# F408HS_control.net
KiCad netlist of a schematic drawn in EAGLE
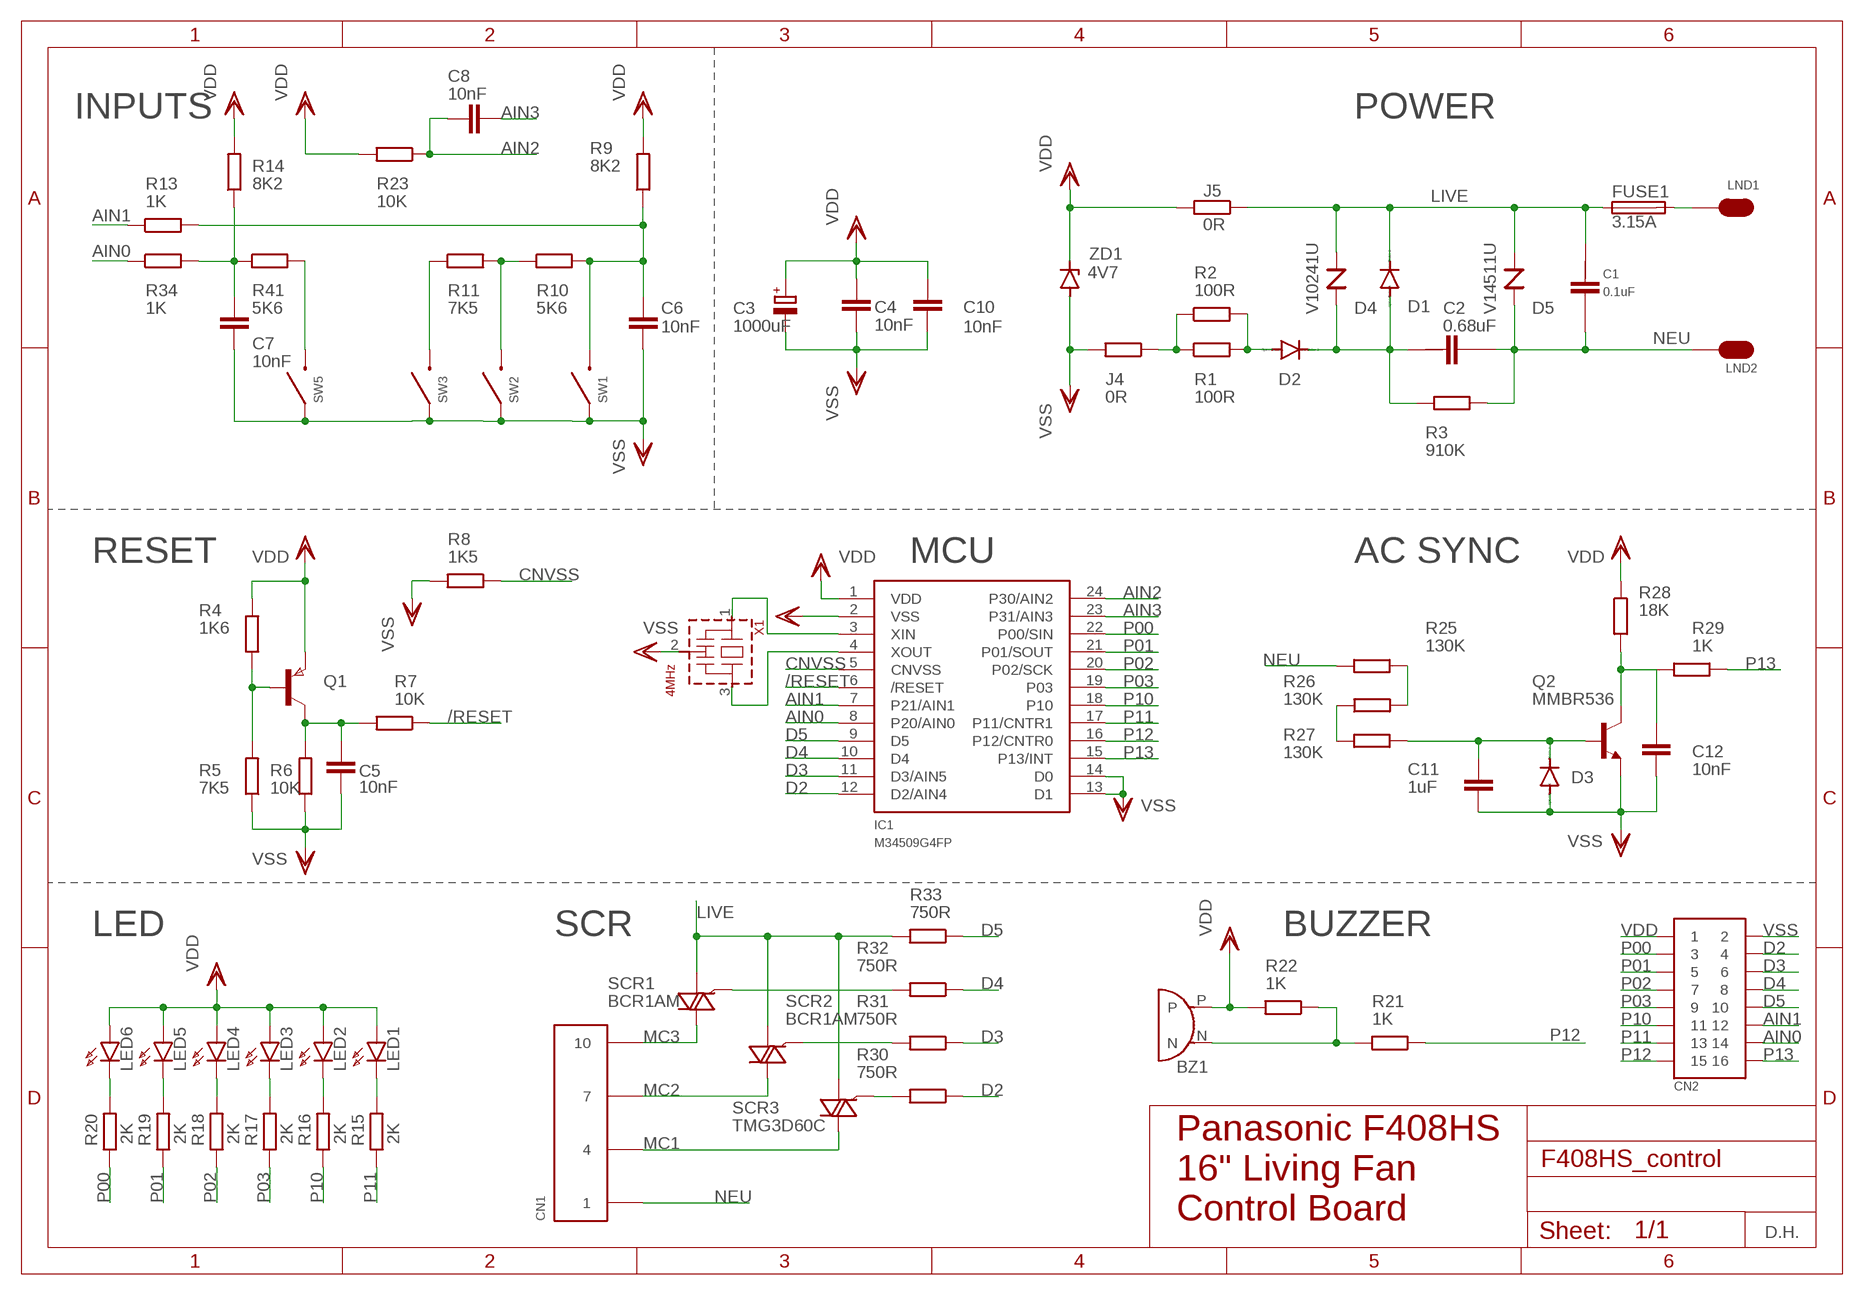
[diagram p0: schematic, sheet 1]

(export (version "E")
  (design (tool "Eeschema 10.0.6"))
  (components
    (comp (ref "BZ1")
      (value "BUZZER")
      (footprint "eagle-import:BUZZER")
      (libsource (lib "eagle-import") (part "BUZZER"))
    )
    (comp (ref "C1")
      (value "0.1uF")
      (footprint "eagle-import:ECQU2A104")
      (libsource (lib "eagle-import") (part "ECQU2A104"))
    )
    (comp (ref "C2")
      (value "0.68uF")
      (footprint "eagle-import:ECQU2A684")
      (libsource (lib "eagle-import") (part "ECQUL2A648KL"))
    )
    (comp (ref "C3")
      (value "1000uF")
      (footprint "eagle-import:B45181B")
      (libsource (lib "eagle-import") (part "CPOL-EUB45181B"))
    )
    (comp (ref "C4")
      (value "10nF")
      (footprint "eagle-import:C0805")
      (libsource (lib "eagle-import") (part "C-EUC0805"))
    )
    (comp (ref "C5")
      (value "10nF")
      (footprint "eagle-import:C0805")
      (libsource (lib "eagle-import") (part "C-EUC0805"))
    )
    (comp (ref "C6")
      (value "10nF")
      (footprint "eagle-import:C0805")
      (libsource (lib "eagle-import") (part "C-EUC0805"))
    )
    (comp (ref "C7")
      (value "10nF")
      (footprint "eagle-import:C0805")
      (libsource (lib "eagle-import") (part "C-EUC0805"))
    )
    (comp (ref "C8")
      (value "10nF")
      (footprint "eagle-import:C0805")
      (libsource (lib "eagle-import") (part "C-EUC0805"))
    )
    (comp (ref "C10")
      (value "10nF")
      (footprint "eagle-import:C0805")
      (libsource (lib "eagle-import") (part "C-EUC0805"))
    )
    (comp (ref "C11")
      (value "1uF")
      (footprint "eagle-import:C0805")
      (libsource (lib "eagle-import") (part "C-EUC0805"))
    )
    (comp (ref "C12")
      (value "10nF")
      (footprint "eagle-import:C0805")
      (libsource (lib "eagle-import") (part "C-EUC0805"))
    )
    (comp (ref "CN1")
      (value "SC25-10WS")
      (footprint "eagle-import:SC25-10WS")
      (libsource (lib "eagle-import") (part "SC25-10WS"))
    )
    (comp (ref "CN2")
      (value "HEADER16")
      (footprint "eagle-import:PAK100_2500-16")
      (libsource (lib "eagle-import") (part "HEADER16"))
    )
    (comp (ref "D1")
      (value "SD103CWS-7-F")
      (footprint "eagle-import:DO41-10")
      (libsource (lib "eagle-import") (part "1N4004"))
    )
    (comp (ref "D2")
      (value "SD103CWS-7-F")
      (footprint "eagle-import:DO41-10")
      (libsource (lib "eagle-import") (part "1N4004"))
    )
    (comp (ref "D3")
      (value "DIODE-SOD106-W")
      (footprint "eagle-import:SOD106-W")
      (libsource (lib "eagle-import") (part "DIODE-SOD106-W"))
    )
    (comp (ref "D4")
      (value "V10241U")
      (footprint "eagle-import:E14-S1")
      (libsource (lib "eagle-import") (part "TVS"))
    )
    (comp (ref "D5")
      (value "V14511U")
      (footprint "eagle-import:E14-S1")
      (libsource (lib "eagle-import") (part "TVS"))
    )
    (comp (ref "FUSE1")
      (value "3.15A")
      (footprint "eagle-import:FUSE")
      (libsource (lib "eagle-import") (part "FUSE"))
    )
    (comp (ref "IC1")
      (value "M34509G4FP")
      (footprint "eagle-import:SSOP24")
      (libsource (lib "eagle-import") (part "M34509G4FP"))
    )
    (comp (ref "J4")
      (value "0R")
      (footprint "eagle-import:M0805")
      (libsource (lib "eagle-import") (part "R-EU_M0805"))
    )
    (comp (ref "J5")
      (value "0R")
      (footprint "eagle-import:M0805")
      (libsource (lib "eagle-import") (part "R-EU_M0805"))
    )
    (comp (ref "LED1")
      (value "LED_PTH_HORIZ")
      (footprint "eagle-import:LED_HORIZ")
      (libsource (lib "eagle-import") (part "LED_PTH_HORIZ"))
    )
    (comp (ref "LED2")
      (value "LED_PTH_HORIZ")
      (footprint "eagle-import:LED_HORIZ")
      (libsource (lib "eagle-import") (part "LED_PTH_HORIZ"))
    )
    (comp (ref "LED3")
      (value "LED_PTH_HORIZ")
      (footprint "eagle-import:LED_HORIZ")
      (libsource (lib "eagle-import") (part "LED_PTH_HORIZ"))
    )
    (comp (ref "LED4")
      (value "LED_PTH_HORIZ")
      (footprint "eagle-import:LED_HORIZ")
      (libsource (lib "eagle-import") (part "LED_PTH_HORIZ"))
    )
    (comp (ref "LED5")
      (value "LED_PTH_HORIZ")
      (footprint "eagle-import:LED_HORIZ")
      (libsource (lib "eagle-import") (part "LED_PTH_HORIZ"))
    )
    (comp (ref "LED6")
      (value "LED_PTH_HORIZ")
      (footprint "eagle-import:LED_HORIZ")
      (libsource (lib "eagle-import") (part "LED_PTH_HORIZ"))
    )
    (comp (ref "LND1")
      (value "LND")
      (footprint "eagle-import:LND")
      (libsource (lib "eagle-import") (part "LND"))
    )
    (comp (ref "LND2")
      (value "LND")
      (footprint "eagle-import:LND")
      (libsource (lib "eagle-import") (part "LND"))
    )
    (comp (ref "Q1")
      (value "PNPSOT23")
      (footprint "eagle-import:SOT-23")
      (fields (field (name "MPN") "DSS20200L-7"))
      (libsource (lib "eagle-import") (part "PNPSOT23"))
    )
    (comp (ref "Q2")
      (value "MMBR536")
      (footprint "eagle-import:SOT23")
      (libsource (lib "eagle-import") (part "MMBR536"))
    )
    (comp (ref "R1")
      (value "100R")
      (footprint "eagle-import:0204_7")
      (libsource (lib "eagle-import") (part "R-EU_0204/7"))
    )
    (comp (ref "R2")
      (value "100R")
      (footprint "eagle-import:0204_7")
      (libsource (lib "eagle-import") (part "R-EU_0204/7"))
    )
    (comp (ref "R3")
      (value "910K")
      (footprint "eagle-import:0204_7")
      (libsource (lib "eagle-import") (part "R-EU_0204/7"))
    )
    (comp (ref "R4")
      (value "1K6")
      (footprint "eagle-import:M0805")
      (libsource (lib "eagle-import") (part "R-EU_M0805"))
    )
    (comp (ref "R5")
      (value "7K5")
      (footprint "eagle-import:M0805")
      (libsource (lib "eagle-import") (part "R-EU_M0805"))
    )
    (comp (ref "R6")
      (value "10K")
      (footprint "eagle-import:M0805")
      (libsource (lib "eagle-import") (part "R-EU_M0805"))
    )
    (comp (ref "R7")
      (value "10K")
      (footprint "eagle-import:M0805")
      (libsource (lib "eagle-import") (part "R-EU_M0805"))
    )
    (comp (ref "R8")
      (value "1K5")
      (footprint "eagle-import:M0805")
      (libsource (lib "eagle-import") (part "R-EU_M0805"))
    )
    (comp (ref "R9")
      (value "8K2")
      (footprint "eagle-import:M0805")
      (libsource (lib "eagle-import") (part "R-EU_M0805"))
    )
    (comp (ref "R10")
      (value "5K6")
      (footprint "eagle-import:M0805")
      (libsource (lib "eagle-import") (part "R-EU_M0805"))
    )
    (comp (ref "R11")
      (value "7K5")
      (footprint "eagle-import:M0805")
      (libsource (lib "eagle-import") (part "R-EU_M0805"))
    )
    (comp (ref "R13")
      (value "1K")
      (footprint "eagle-import:M0805")
      (libsource (lib "eagle-import") (part "R-EU_M0805"))
    )
    (comp (ref "R14")
      (value "8K2")
      (footprint "eagle-import:M0805")
      (libsource (lib "eagle-import") (part "R-EU_M0805"))
    )
    (comp (ref "R15")
      (value "2K")
      (footprint "eagle-import:M0805")
      (libsource (lib "eagle-import") (part "R-EU_M0805"))
    )
    (comp (ref "R16")
      (value "2K")
      (footprint "eagle-import:M0805")
      (libsource (lib "eagle-import") (part "R-EU_M0805"))
    )
    (comp (ref "R17")
      (value "2K")
      (footprint "eagle-import:M0805")
      (libsource (lib "eagle-import") (part "R-EU_M0805"))
    )
    (comp (ref "R18")
      (value "2K")
      (footprint "eagle-import:M0805")
      (libsource (lib "eagle-import") (part "R-EU_M0805"))
    )
    (comp (ref "R19")
      (value "2K")
      (footprint "eagle-import:M0805")
      (libsource (lib "eagle-import") (part "R-EU_M0805"))
    )
    (comp (ref "R20")
      (value "2K")
      (footprint "eagle-import:M0805")
      (libsource (lib "eagle-import") (part "R-EU_M0805"))
    )
    (comp (ref "R21")
      (value "1K")
      (footprint "eagle-import:M0805")
      (libsource (lib "eagle-import") (part "R-EU_M0805"))
    )
    (comp (ref "R22")
      (value "1K")
      (footprint "eagle-import:M0805")
      (libsource (lib "eagle-import") (part "R-EU_M0805"))
    )
    (comp (ref "R23")
      (value "10K")
      (footprint "eagle-import:M0805")
      (libsource (lib "eagle-import") (part "R-EU_M0805"))
    )
    (comp (ref "R25")
      (value "130K")
      (footprint "eagle-import:R0805")
      (libsource (lib "eagle-import") (part "R-EU_R0805"))
    )
    (comp (ref "R26")
      (value "130K")
      (footprint "eagle-import:R0805")
      (libsource (lib "eagle-import") (part "R-EU_R0805"))
    )
    (comp (ref "R27")
      (value "130K")
      (footprint "eagle-import:R0805")
      (libsource (lib "eagle-import") (part "R-EU_R0805"))
    )
    (comp (ref "R28")
      (value "18K")
      (footprint "eagle-import:M0805")
      (libsource (lib "eagle-import") (part "R-EU_M0805"))
    )
    (comp (ref "R29")
      (value "1K")
      (footprint "eagle-import:M0805")
      (libsource (lib "eagle-import") (part "R-EU_M0805"))
    )
    (comp (ref "R30")
      (value "750R")
      (footprint "eagle-import:M0805")
      (libsource (lib "eagle-import") (part "R-EU_M0805"))
    )
    (comp (ref "R31")
      (value "750R")
      (footprint "eagle-import:M0805")
      (libsource (lib "eagle-import") (part "R-EU_M0805"))
    )
    (comp (ref "R32")
      (value "750R")
      (footprint "eagle-import:M0805")
      (libsource (lib "eagle-import") (part "R-EU_M0805"))
    )
    (comp (ref "R33")
      (value "750R")
      (footprint "eagle-import:M0805")
      (libsource (lib "eagle-import") (part "R-EU_M0805"))
    )
    (comp (ref "R34")
      (value "1K")
      (footprint "eagle-import:M0805")
      (libsource (lib "eagle-import") (part "R-EU_M0805"))
    )
    (comp (ref "R41")
      (value "5K6")
      (footprint "eagle-import:M0805")
      (libsource (lib "eagle-import") (part "R-EU_M0805"))
    )
    (comp (ref "SCR1")
      (value "BCR1AM")
      (footprint "eagle-import:TO92")
      (libsource (lib "eagle-import") (part "BCR1AM"))
    )
    (comp (ref "SCR2")
      (value "BCR1AM")
      (footprint "eagle-import:TO92")
      (libsource (lib "eagle-import") (part "BCR1AM"))
    )
    (comp (ref "SCR3")
      (value "TMG3D60C")
      (footprint "eagle-import:TO220DS")
      (libsource (lib "eagle-import") (part "TIC225S"))
    )
    (comp (ref "SW1")
      (value "EVQ11")
      (footprint "eagle-import:EVQ11")
      (libsource (lib "eagle-import") (part "EVQ11"))
    )
    (comp (ref "SW2")
      (value "EVQ11")
      (footprint "eagle-import:EVQ11")
      (libsource (lib "eagle-import") (part "EVQ11"))
    )
    (comp (ref "SW3")
      (value "EVQ11")
      (footprint "eagle-import:EVQ11")
      (libsource (lib "eagle-import") (part "EVQ11"))
    )
    (comp (ref "SW5")
      (value "EVQ11")
      (footprint "eagle-import:EVQ11")
      (libsource (lib "eagle-import") (part "EVQ11"))
    )
    (comp (ref "X1")
      (value "4MHz")
      (footprint "eagle-import:CSTLS_G9")
      (libsource (lib "eagle-import") (part "murata-resonators_CSTLS_G"))
    )
    (comp (ref "ZD1")
      (value "DDZ4V7ASF-7")
      (footprint "eagle-import:DO35Z10")
      (libsource (lib "eagle-import") (part "1N821"))
    )
  )
  (nets
    (net (code "1") (name "/AIN0") (class "Default")
      (node (ref "CN2") (pin "14") (pinfunction "14_14") (pintype "bidirectional"))
      (node (ref "IC1") (pin "8") (pinfunction "P20/AIN0_8") (pintype "bidirectional"))
      (node (ref "R34") (pin "1") (pinfunction "1_1") (pintype "passive"))
    )
    (net (code "2") (name "/AIN1") (class "Default")
      (node (ref "CN2") (pin "12") (pinfunction "12_12") (pintype "bidirectional"))
      (node (ref "IC1") (pin "7") (pinfunction "P21/AIN1_7") (pintype "bidirectional"))
      (node (ref "R13") (pin "1") (pinfunction "1_1") (pintype "passive"))
    )
    (net (code "3") (name "/AIN2") (class "Default")
      (node (ref "C8") (pin "1") (pinfunction "1_1") (pintype "passive"))
      (node (ref "IC1") (pin "24") (pinfunction "P30/AIN2_24") (pintype "bidirectional"))
      (node (ref "R23") (pin "1") (pinfunction "1_1") (pintype "passive"))
    )
    (net (code "4") (name "/AIN3") (class "Default")
      (node (ref "C8") (pin "2") (pinfunction "2_2") (pintype "passive"))
      (node (ref "IC1") (pin "23") (pinfunction "P31/AIN3_23") (pintype "bidirectional"))
    )
    (net (code "5") (name "/CNVSS") (class "Default")
      (node (ref "IC1") (pin "5") (pinfunction "CNVSS_5") (pintype "bidirectional"))
      (node (ref "R8") (pin "1") (pinfunction "1_1") (pintype "passive"))
    )
    (net (code "6") (name "/D2") (class "Default")
      (node (ref "CN2") (pin "4") (pinfunction "4_4") (pintype "bidirectional"))
      (node (ref "IC1") (pin "12") (pinfunction "D2/AIN4_12") (pintype "bidirectional"))
      (node (ref "R30") (pin "1") (pinfunction "1_1") (pintype "passive"))
    )
    (net (code "7") (name "/D3") (class "Default")
      (node (ref "CN2") (pin "6") (pinfunction "6_6") (pintype "bidirectional"))
      (node (ref "IC1") (pin "11") (pinfunction "D3/AIN5_11") (pintype "bidirectional"))
      (node (ref "R31") (pin "1") (pinfunction "1_1") (pintype "passive"))
    )
    (net (code "8") (name "/D4") (class "Default")
      (node (ref "CN2") (pin "8") (pinfunction "8_8") (pintype "bidirectional"))
      (node (ref "IC1") (pin "10") (pinfunction "D4_10") (pintype "bidirectional"))
      (node (ref "R32") (pin "1") (pinfunction "1_1") (pintype "passive"))
    )
    (net (code "9") (name "/D5") (class "Default")
      (node (ref "CN2") (pin "10") (pinfunction "10_10") (pintype "bidirectional"))
      (node (ref "IC1") (pin "9") (pinfunction "D5_9") (pintype "bidirectional"))
      (node (ref "R33") (pin "1") (pinfunction "1_1") (pintype "passive"))
    )
    (net (code "10") (name "/LIVE") (class "Default")
      (node (ref "C1") (pin "P$1") (pinfunction "P$1_P$1") (pintype "bidirectional"))
      (node (ref "D1") (pin "C") (pinfunction "C_C") (pintype "passive"))
      (node (ref "D4") (pin "P$1") (pinfunction "P$1_P$1") (pintype "bidirectional"))
      (node (ref "D5") (pin "P$1") (pinfunction "P$1_P$1") (pintype "bidirectional"))
      (node (ref "FUSE1") (pin "P$1") (pinfunction "1_P$1") (pintype "passive"))
      (node (ref "J5") (pin "1") (pinfunction "1_1") (pintype "passive"))
      (node (ref "R33") (pin "2") (pinfunction "2_2") (pintype "passive"))
      (node (ref "SCR1") (pin "1") (pinfunction "A1_1") (pintype "passive"))
      (node (ref "SCR2") (pin "1") (pinfunction "A1_1") (pintype "passive"))
      (node (ref "SCR3") (pin "A1") (pinfunction "A1_A1") (pintype "passive"))
    )
    (net (code "11") (name "/MC1") (class "Default")
      (node (ref "CN1") (pin "P$4") (pinfunction "4_P$4") (pintype "bidirectional"))
      (node (ref "SCR3") (pin "A2") (pinfunction "A2_A2") (pintype "passive"))
    )
    (net (code "12") (name "/MC2") (class "Default")
      (node (ref "CN1") (pin "P$7") (pinfunction "7_P$7") (pintype "bidirectional"))
      (node (ref "SCR2") (pin "3") (pinfunction "A2_3") (pintype "passive"))
    )
    (net (code "13") (name "/MC3") (class "Default")
      (node (ref "CN1") (pin "P$10") (pinfunction "10_P$10") (pintype "bidirectional"))
      (node (ref "SCR1") (pin "3") (pinfunction "A2_3") (pintype "passive"))
    )
    (net (code "14") (name "/NEU") (class "Default")
      (node (ref "C1") (pin "P$2") (pinfunction "P$2_P$2") (pintype "bidirectional"))
      (node (ref "C2") (pin "P$2") (pinfunction "P$2_P$2") (pintype "bidirectional"))
      (node (ref "CN1") (pin "P$1") (pinfunction "1_P$1") (pintype "bidirectional"))
      (node (ref "D5") (pin "P$2") (pinfunction "P$2_P$2") (pintype "bidirectional"))
      (node (ref "LND2") (pin "P$1") (pinfunction "P$1_P$1") (pintype "bidirectional"))
      (node (ref "R25") (pin "2") (pinfunction "2_2") (pintype "passive"))
      (node (ref "R3") (pin "2") (pinfunction "2_2") (pintype "passive"))
    )
    (net (code "15") (name "/P00") (class "Default")
      (node (ref "CN2") (pin "3") (pinfunction "3_3") (pintype "bidirectional"))
      (node (ref "IC1") (pin "22") (pinfunction "P00/SIN_22") (pintype "bidirectional"))
      (node (ref "R20") (pin "1") (pinfunction "1_1") (pintype "passive"))
    )
    (net (code "16") (name "/P01") (class "Default")
      (node (ref "CN2") (pin "5") (pinfunction "5_5") (pintype "bidirectional"))
      (node (ref "IC1") (pin "21") (pinfunction "P01/SOUT_21") (pintype "bidirectional"))
      (node (ref "R19") (pin "1") (pinfunction "1_1") (pintype "passive"))
    )
    (net (code "17") (name "/P02") (class "Default")
      (node (ref "CN2") (pin "7") (pinfunction "7_7") (pintype "bidirectional"))
      (node (ref "IC1") (pin "20") (pinfunction "P02/SCK_20") (pintype "bidirectional"))
      (node (ref "R18") (pin "1") (pinfunction "1_1") (pintype "passive"))
    )
    (net (code "18") (name "/P03") (class "Default")
      (node (ref "CN2") (pin "9") (pinfunction "9_9") (pintype "bidirectional"))
      (node (ref "IC1") (pin "19") (pinfunction "P03_19") (pintype "bidirectional"))
      (node (ref "R17") (pin "1") (pinfunction "1_1") (pintype "passive"))
    )
    (net (code "19") (name "/P10") (class "Default")
      (node (ref "CN2") (pin "11") (pinfunction "11_11") (pintype "bidirectional"))
      (node (ref "IC1") (pin "18") (pinfunction "P10_18") (pintype "bidirectional"))
      (node (ref "R16") (pin "1") (pinfunction "1_1") (pintype "passive"))
    )
    (net (code "20") (name "/P11") (class "Default")
      (node (ref "CN2") (pin "13") (pinfunction "13_13") (pintype "bidirectional"))
      (node (ref "IC1") (pin "17") (pinfunction "P11/CNTR1_17") (pintype "bidirectional"))
      (node (ref "R15") (pin "1") (pinfunction "1_1") (pintype "passive"))
    )
    (net (code "21") (name "/P12") (class "Default")
      (node (ref "CN2") (pin "15") (pinfunction "15_15") (pintype "bidirectional"))
      (node (ref "IC1") (pin "16") (pinfunction "P12/CNTR0_16") (pintype "bidirectional"))
      (node (ref "R21") (pin "1") (pinfunction "1_1") (pintype "passive"))
    )
    (net (code "22") (name "/P13") (class "Default")
      (node (ref "CN2") (pin "16") (pinfunction "16_16") (pintype "bidirectional"))
      (node (ref "IC1") (pin "15") (pinfunction "P13/INT_15") (pintype "bidirectional"))
      (node (ref "R29") (pin "1") (pinfunction "1_1") (pintype "passive"))
    )
    (net (code "23") (name "/{slash}RESET") (class "Default")
      (node (ref "IC1") (pin "6") (pinfunction "/RESET_6") (pintype "bidirectional"))
      (node (ref "R7") (pin "1") (pinfunction "1_1") (pintype "passive"))
    )
    (net (code "24") (name "Net-(BZ1-PadN)") (class "Default")
      (node (ref "BZ1") (pin "N") (pinfunction "N_N") (pintype "bidirectional"))
      (node (ref "R21") (pin "2") (pinfunction "2_2") (pintype "passive"))
      (node (ref "R22") (pin "1") (pinfunction "1_1") (pintype "passive"))
    )
    (net (code "25") (name "Net-(C2-PadP$1)") (class "Default")
      (node (ref "C2") (pin "P$1") (pinfunction "P$1_P$1") (pintype "bidirectional"))
      (node (ref "D1") (pin "A") (pinfunction "A_A") (pintype "passive"))
      (node (ref "D2") (pin "C") (pinfunction "C_C") (pintype "passive"))
      (node (ref "D4") (pin "P$2") (pinfunction "P$2_P$2") (pintype "bidirectional"))
      (node (ref "R3") (pin "1") (pinfunction "1_1") (pintype "passive"))
    )
    (net (code "26") (name "Net-(C6-Pad2)") (class "Default")
      (node (ref "C6") (pin "2") (pinfunction "2_2") (pintype "passive"))
      (node (ref "R10") (pin "2") (pinfunction "2_2") (pintype "passive"))
      (node (ref "R13") (pin "2") (pinfunction "2_2") (pintype "passive"))
      (node (ref "R9") (pin "1") (pinfunction "1_1") (pintype "passive"))
      (node (ref "SW1") (pin "P$2") (pinfunction "P$2_P$2") (pintype "bidirectional"))
    )
    (net (code "27") (name "Net-(C7-Pad1)") (class "Default")
      (node (ref "C7") (pin "1") (pinfunction "1_1") (pintype "passive"))
      (node (ref "R14") (pin "1") (pinfunction "1_1") (pintype "passive"))
      (node (ref "R34") (pin "2") (pinfunction "2_2") (pintype "passive"))
      (node (ref "R41") (pin "1") (pinfunction "1_1") (pintype "passive"))
    )
    (net (code "28") (name "Net-(D2-PadA)") (class "Default")
      (node (ref "D2") (pin "A") (pinfunction "A_A") (pintype "passive"))
      (node (ref "R1") (pin "2") (pinfunction "2_2") (pintype "passive"))
      (node (ref "R2") (pin "2") (pinfunction "2_2") (pintype "passive"))
    )
    (net (code "29") (name "Net-(FUSE1-2)") (class "Default")
      (node (ref "FUSE1") (pin "P$2") (pinfunction "2_P$2") (pintype "passive"))
      (node (ref "LND1") (pin "P$1") (pinfunction "P$1_P$1") (pintype "bidirectional"))
    )
    (net (code "30") (name "Net-(IC1-XIN)") (class "Default")
      (node (ref "IC1") (pin "3") (pinfunction "XIN_3") (pintype "bidirectional"))
      (node (ref "X1") (pin "1") (pinfunction "1_1") (pintype "output"))
    )
    (net (code "31") (name "Net-(IC1-XOUT)") (class "Default")
      (node (ref "IC1") (pin "4") (pinfunction "XOUT_4") (pintype "bidirectional"))
      (node (ref "X1") (pin "3") (pinfunction "3_3") (pintype "input"))
    )
    (net (code "32") (name "Net-(J4-Pad1)") (class "Default")
      (node (ref "J4") (pin "1") (pinfunction "1_1") (pintype "passive"))
      (node (ref "R1") (pin "1") (pinfunction "1_1") (pintype "passive"))
      (node (ref "R2") (pin "1") (pinfunction "1_1") (pintype "passive"))
    )
    (net (code "33") (name "Net-(LED1-K)") (class "Default")
      (node (ref "LED1") (pin "N") (pinfunction "K_N") (pintype "passive"))
      (node (ref "R15") (pin "2") (pinfunction "2_2") (pintype "passive"))
    )
    (net (code "34") (name "Net-(LED2-K)") (class "Default")
      (node (ref "LED2") (pin "N") (pinfunction "K_N") (pintype "passive"))
      (node (ref "R16") (pin "2") (pinfunction "2_2") (pintype "passive"))
    )
    (net (code "35") (name "Net-(LED3-K)") (class "Default")
      (node (ref "LED3") (pin "N") (pinfunction "K_N") (pintype "passive"))
      (node (ref "R17") (pin "2") (pinfunction "2_2") (pintype "passive"))
    )
    (net (code "36") (name "Net-(LED4-K)") (class "Default")
      (node (ref "LED4") (pin "N") (pinfunction "K_N") (pintype "passive"))
      (node (ref "R18") (pin "2") (pinfunction "2_2") (pintype "passive"))
    )
    (net (code "37") (name "Net-(LED5-K)") (class "Default")
      (node (ref "LED5") (pin "N") (pinfunction "K_N") (pintype "passive"))
      (node (ref "R19") (pin "2") (pinfunction "2_2") (pintype "passive"))
    )
    (net (code "38") (name "Net-(LED6-K)") (class "Default")
      (node (ref "LED6") (pin "N") (pinfunction "K_N") (pintype "passive"))
      (node (ref "R20") (pin "2") (pinfunction "2_2") (pintype "passive"))
    )
    (net (code "39") (name "Net-(Q1-B)") (class "Default")
      (node (ref "Q1") (pin "3") (pinfunction "B_3") (pintype "passive"))
      (node (ref "R4") (pin "1") (pinfunction "1_1") (pintype "passive"))
      (node (ref "R5") (pin "2") (pinfunction "2_2") (pintype "passive"))
    )
    (net (code "40") (name "Net-(Q1-C)") (class "Default")
      (node (ref "C5") (pin "1") (pinfunction "1_1") (pintype "passive"))
      (node (ref "Q1") (pin "1") (pinfunction "C_1") (pintype "passive"))
      (node (ref "R6") (pin "2") (pinfunction "2_2") (pintype "passive"))
      (node (ref "R7") (pin "2") (pinfunction "2_2") (pintype "passive"))
    )
    (net (code "41") (name "Net-(Q2-B)") (class "Default")
      (node (ref "C11") (pin "2") (pinfunction "2_2") (pintype "passive"))
      (node (ref "D3") (pin "C") (pinfunction "C_C") (pintype "passive"))
      (node (ref "Q2") (pin "1") (pinfunction "B_1") (pintype "passive"))
      (node (ref "R27") (pin "1") (pinfunction "1_1") (pintype "passive"))
    )
    (net (code "42") (name "Net-(Q2-C)") (class "Default")
      (node (ref "C12") (pin "2") (pinfunction "2_2") (pintype "passive"))
      (node (ref "Q2") (pin "3") (pinfunction "C_3") (pintype "passive"))
      (node (ref "R28") (pin "2") (pinfunction "2_2") (pintype "passive"))
      (node (ref "R29") (pin "2") (pinfunction "2_2") (pintype "passive"))
    )
    (net (code "43") (name "Net-(R10-Pad1)") (class "Default")
      (node (ref "R10") (pin "1") (pinfunction "1_1") (pintype "passive"))
      (node (ref "R11") (pin "2") (pinfunction "2_2") (pintype "passive"))
      (node (ref "SW2") (pin "P$2") (pinfunction "P$2_P$2") (pintype "bidirectional"))
    )
    (net (code "44") (name "Net-(R11-Pad1)") (class "Default")
      (node (ref "R11") (pin "1") (pinfunction "1_1") (pintype "passive"))
      (node (ref "SW3") (pin "P$2") (pinfunction "P$2_P$2") (pintype "bidirectional"))
    )
    (net (code "45") (name "Net-(R25-Pad1)") (class "Default")
      (node (ref "R25") (pin "1") (pinfunction "1_1") (pintype "passive"))
      (node (ref "R26") (pin "2") (pinfunction "2_2") (pintype "passive"))
    )
    (net (code "46") (name "Net-(R26-Pad1)") (class "Default")
      (node (ref "R26") (pin "1") (pinfunction "1_1") (pintype "passive"))
      (node (ref "R27") (pin "2") (pinfunction "2_2") (pintype "passive"))
    )
    (net (code "47") (name "Net-(R30-Pad2)") (class "Default")
      (node (ref "R30") (pin "2") (pinfunction "2_2") (pintype "passive"))
      (node (ref "SCR3") (pin "G") (pinfunction "G_G") (pintype "passive"))
    )
    (net (code "48") (name "Net-(R41-Pad2)") (class "Default")
      (node (ref "R41") (pin "2") (pinfunction "2_2") (pintype "passive"))
      (node (ref "SW5") (pin "P$2") (pinfunction "P$2_P$2") (pintype "bidirectional"))
    )
    (net (code "49") (name "Net-(SCR1-G)") (class "Default")
      (node (ref "R32") (pin "2") (pinfunction "2_2") (pintype "passive"))
      (node (ref "SCR1") (pin "2") (pinfunction "G_2") (pintype "passive"))
    )
    (net (code "50") (name "Net-(SCR2-G)") (class "Default")
      (node (ref "R31") (pin "2") (pinfunction "2_2") (pintype "passive"))
      (node (ref "SCR2") (pin "2") (pinfunction "G_2") (pintype "passive"))
    )
    (net (code "51") (name "VDD") (class "Default")
      (node (ref "BZ1") (pin "P") (pinfunction "P_P") (pintype "bidirectional"))
      (node (ref "C10") (pin "1") (pinfunction "1_1") (pintype "passive"))
      (node (ref "C3") (pin "+") (pinfunction "+_+") (pintype "passive"))
      (node (ref "C4") (pin "1") (pinfunction "1_1") (pintype "passive"))
      (node (ref "CN2") (pin "1") (pinfunction "1_1") (pintype "bidirectional"))
      (node (ref "IC1") (pin "1") (pinfunction "VDD_1") (pintype "bidirectional"))
      (node (ref "J5") (pin "2") (pinfunction "2_2") (pintype "passive"))
      (node (ref "LED1") (pin "P") (pinfunction "A_P") (pintype "passive"))
      (node (ref "LED2") (pin "P") (pinfunction "A_P") (pintype "passive"))
      (node (ref "LED3") (pin "P") (pinfunction "A_P") (pintype "passive"))
      (node (ref "LED4") (pin "P") (pinfunction "A_P") (pintype "passive"))
      (node (ref "LED5") (pin "P") (pinfunction "A_P") (pintype "passive"))
      (node (ref "LED6") (pin "P") (pinfunction "A_P") (pintype "passive"))
      (node (ref "Q1") (pin "2") (pinfunction "E_2") (pintype "passive"))
      (node (ref "R14") (pin "2") (pinfunction "2_2") (pintype "passive"))
      (node (ref "R22") (pin "2") (pinfunction "2_2") (pintype "passive"))
      (node (ref "R23") (pin "2") (pinfunction "2_2") (pintype "passive"))
      (node (ref "R28") (pin "1") (pinfunction "1_1") (pintype "passive"))
      (node (ref "R4") (pin "2") (pinfunction "2_2") (pintype "passive"))
      (node (ref "R9") (pin "2") (pinfunction "2_2") (pintype "passive"))
      (node (ref "ZD1") (pin "C") (pinfunction "C_C") (pintype "passive"))
    )
    (net (code "52") (name "VSS") (class "Default")
      (node (ref "C10") (pin "2") (pinfunction "2_2") (pintype "passive"))
      (node (ref "C11") (pin "1") (pinfunction "1_1") (pintype "passive"))
      (node (ref "C12") (pin "1") (pinfunction "1_1") (pintype "passive"))
      (node (ref "C3") (pin "-") (pinfunction "-_-") (pintype "passive"))
      (node (ref "C4") (pin "2") (pinfunction "2_2") (pintype "passive"))
      (node (ref "C5") (pin "2") (pinfunction "2_2") (pintype "passive"))
      (node (ref "C6") (pin "1") (pinfunction "1_1") (pintype "passive"))
      (node (ref "C7") (pin "2") (pinfunction "2_2") (pintype "passive"))
      (node (ref "CN2") (pin "2") (pinfunction "2_2") (pintype "bidirectional"))
      (node (ref "D3") (pin "A") (pinfunction "A_A") (pintype "passive"))
      (node (ref "IC1") (pin "13") (pinfunction "D1_13") (pintype "bidirectional"))
      (node (ref "IC1") (pin "14") (pinfunction "D0_14") (pintype "bidirectional"))
      (node (ref "IC1") (pin "2") (pinfunction "VSS_2") (pintype "bidirectional"))
      (node (ref "J4") (pin "2") (pinfunction "2_2") (pintype "passive"))
      (node (ref "Q2") (pin "2") (pinfunction "E_2") (pintype "passive"))
      (node (ref "R5") (pin "1") (pinfunction "1_1") (pintype "passive"))
      (node (ref "R6") (pin "1") (pinfunction "1_1") (pintype "passive"))
      (node (ref "R8") (pin "2") (pinfunction "2_2") (pintype "passive"))
      (node (ref "SW1") (pin "P$1") (pinfunction "P$1_P$1") (pintype "bidirectional"))
      (node (ref "SW2") (pin "P$1") (pinfunction "P$1_P$1") (pintype "bidirectional"))
      (node (ref "SW3") (pin "P$1") (pinfunction "P$1_P$1") (pintype "bidirectional"))
      (node (ref "SW5") (pin "P$1") (pinfunction "P$1_P$1") (pintype "bidirectional"))
      (node (ref "X1") (pin "2") (pinfunction "VSS_2") (pintype "power_in"))
      (node (ref "ZD1") (pin "A") (pinfunction "A_A") (pintype "passive"))
    )
  )
)
